# Beleuchtung.net
KiCad netlist of a schematic drawn in Altium Designer
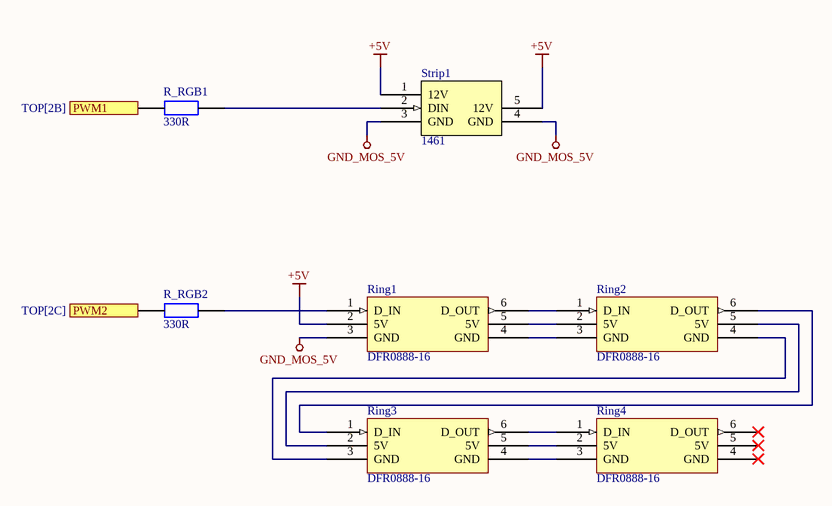
[diagram p0: Beleuchtung.SchDoc]

(export (version "E")
  (design (tool "Eeschema 10.0.6"))
  (components
    (comp (ref "Ring1")
      (value "DFR0888-16")
      (description "DFRobot, DFR0888-16.  \r\nWS2812-16 RGB LED RING LAMP")
      (libsource (lib "3D_Scanner") (part "RGB Ring"))
    )
    (comp (ref "Ring2")
      (value "DFR0888-16")
      (description "DFRobot, DFR0888-16.  \r\nWS2812-16 RGB LED RING LAMP")
      (libsource (lib "3D_Scanner") (part "RGB Ring"))
    )
    (comp (ref "Ring3")
      (value "DFR0888-16")
      (description "DFRobot, DFR0888-16.  \r\nWS2812-16 RGB LED RING LAMP")
      (libsource (lib "3D_Scanner") (part "RGB Ring"))
    )
    (comp (ref "Ring4")
      (value "DFR0888-16")
      (description "DFRobot, DFR0888-16.  \r\nWS2812-16 RGB LED RING LAMP")
      (libsource (lib "3D_Scanner") (part "RGB Ring"))
    )
    (comp (ref "R_RGB1")
      (value "330R")
      (fields (field (name "WIDERSTAND") "330R"))
      (libsource (lib "3D_Scanner") (part "R 330"))
    )
    (comp (ref "R_RGB2")
      (value "330R")
      (fields (field (name "WIDERSTAND") "330R"))
      (libsource (lib "3D_Scanner") (part "R 330"))
    )
    (comp (ref "Strip1")
      (value "1461")
      (description "ADDRESS LED STRIP SERIAL RGB 4M, Adafruit, 1461")
      (libsource (lib "3D_Scanner") (part "RGB Strip"))
    )
  )
  (nets
    (net (code "1") (name "+5V") (class "Default")
      (node (ref "Ring1") (pin "2") (pinfunction "5V_2") (pintype "power_in"))
      (node (ref "Strip1") (pin "1") (pinfunction "12V_1") (pintype "power_in"))
      (node (ref "Strip1") (pin "5") (pinfunction "12V_5") (pintype "power_in"))
    )
    (net (code "2") (name "/PWM1") (class "Default")
      (node (ref "R_RGB1") (pin "0") (pinfunction "0_0") (pintype "passive"))
    )
    (net (code "3") (name "/PWM2") (class "Default")
      (node (ref "R_RGB2") (pin "0") (pinfunction "0_0") (pintype "passive"))
    )
    (net (code "4") (name "GND_MOS_5V") (class "Default")
      (node (ref "Ring1") (pin "3") (pinfunction "GND_3") (pintype "power_in"))
      (node (ref "Strip1") (pin "3") (pinfunction "GND_3") (pintype "power_in"))
      (node (ref "Strip1") (pin "4") (pinfunction "GND_4") (pintype "power_in"))
    )
    (net (code "5") (name "Net-(Ring1-5V-Pad5)") (class "Default")
      (node (ref "Ring1") (pin "5") (pinfunction "5V_5") (pintype "power_in"))
      (node (ref "Ring2") (pin "2") (pinfunction "5V_2") (pintype "power_in"))
    )
    (net (code "6") (name "Net-(Ring1-D_IN)") (class "Default")
      (node (ref "R_RGB2") (pin "1") (pinfunction "1_1") (pintype "passive"))
      (node (ref "Ring1") (pin "1") (pinfunction "D_IN_1") (pintype "input"))
    )
    (net (code "7") (name "Net-(Ring1-D_OUT)") (class "Default")
      (node (ref "Ring1") (pin "6") (pinfunction "D_OUT_6") (pintype "output"))
      (node (ref "Ring2") (pin "1") (pinfunction "D_IN_1") (pintype "input"))
    )
    (net (code "8") (name "Net-(Ring1-GND-Pad4)") (class "Default")
      (node (ref "Ring1") (pin "4") (pinfunction "GND_4") (pintype "power_in"))
      (node (ref "Ring2") (pin "3") (pinfunction "GND_3") (pintype "power_in"))
    )
    (net (code "9") (name "Net-(Ring2-5V-Pad5)") (class "Default")
      (node (ref "Ring2") (pin "5") (pinfunction "5V_5") (pintype "power_in"))
      (node (ref "Ring3") (pin "2") (pinfunction "5V_2") (pintype "power_in"))
    )
    (net (code "10") (name "Net-(Ring2-D_OUT)") (class "Default")
      (node (ref "Ring2") (pin "6") (pinfunction "D_OUT_6") (pintype "output"))
      (node (ref "Ring3") (pin "1") (pinfunction "D_IN_1") (pintype "input"))
    )
    (net (code "11") (name "Net-(Ring2-GND-Pad4)") (class "Default")
      (node (ref "Ring2") (pin "4") (pinfunction "GND_4") (pintype "power_in"))
      (node (ref "Ring3") (pin "3") (pinfunction "GND_3") (pintype "power_in"))
    )
    (net (code "12") (name "Net-(Ring3-5V-Pad5)") (class "Default")
      (node (ref "Ring3") (pin "5") (pinfunction "5V_5") (pintype "power_in"))
      (node (ref "Ring4") (pin "2") (pinfunction "5V_2") (pintype "power_in"))
    )
    (net (code "13") (name "Net-(Ring3-D_OUT)") (class "Default")
      (node (ref "Ring3") (pin "6") (pinfunction "D_OUT_6") (pintype "output"))
      (node (ref "Ring4") (pin "1") (pinfunction "D_IN_1") (pintype "input"))
    )
    (net (code "14") (name "Net-(Ring3-GND-Pad4)") (class "Default")
      (node (ref "Ring3") (pin "4") (pinfunction "GND_4") (pintype "power_in"))
      (node (ref "Ring4") (pin "3") (pinfunction "GND_3") (pintype "power_in"))
    )
    (net (code "15") (name "Net-(Strip1-DIN)") (class "Default")
      (node (ref "R_RGB1") (pin "1") (pinfunction "1_1") (pintype "passive"))
      (node (ref "Strip1") (pin "2") (pinfunction "DIN_2") (pintype "input"))
    )
    (net (code "16") (name "unconnected-(Ring4-5V-Pad5)") (class "Default")
      (node (ref "Ring4") (pin "5") (pinfunction "5V_5") (pintype "power_in+no_connect"))
    )
    (net (code "17") (name "unconnected-(Ring4-D_OUT-Pad6)") (class "Default")
      (node (ref "Ring4") (pin "6") (pinfunction "D_OUT_6") (pintype "output+no_connect"))
    )
    (net (code "18") (name "unconnected-(Ring4-GND-Pad4)") (class "Default")
      (node (ref "Ring4") (pin "4") (pinfunction "GND_4") (pintype "power_in+no_connect"))
    )
  )
)
